# piezo-jfet-buffer-simple-4x.net
KiCad netlist of a schematic drawn in EAGLE
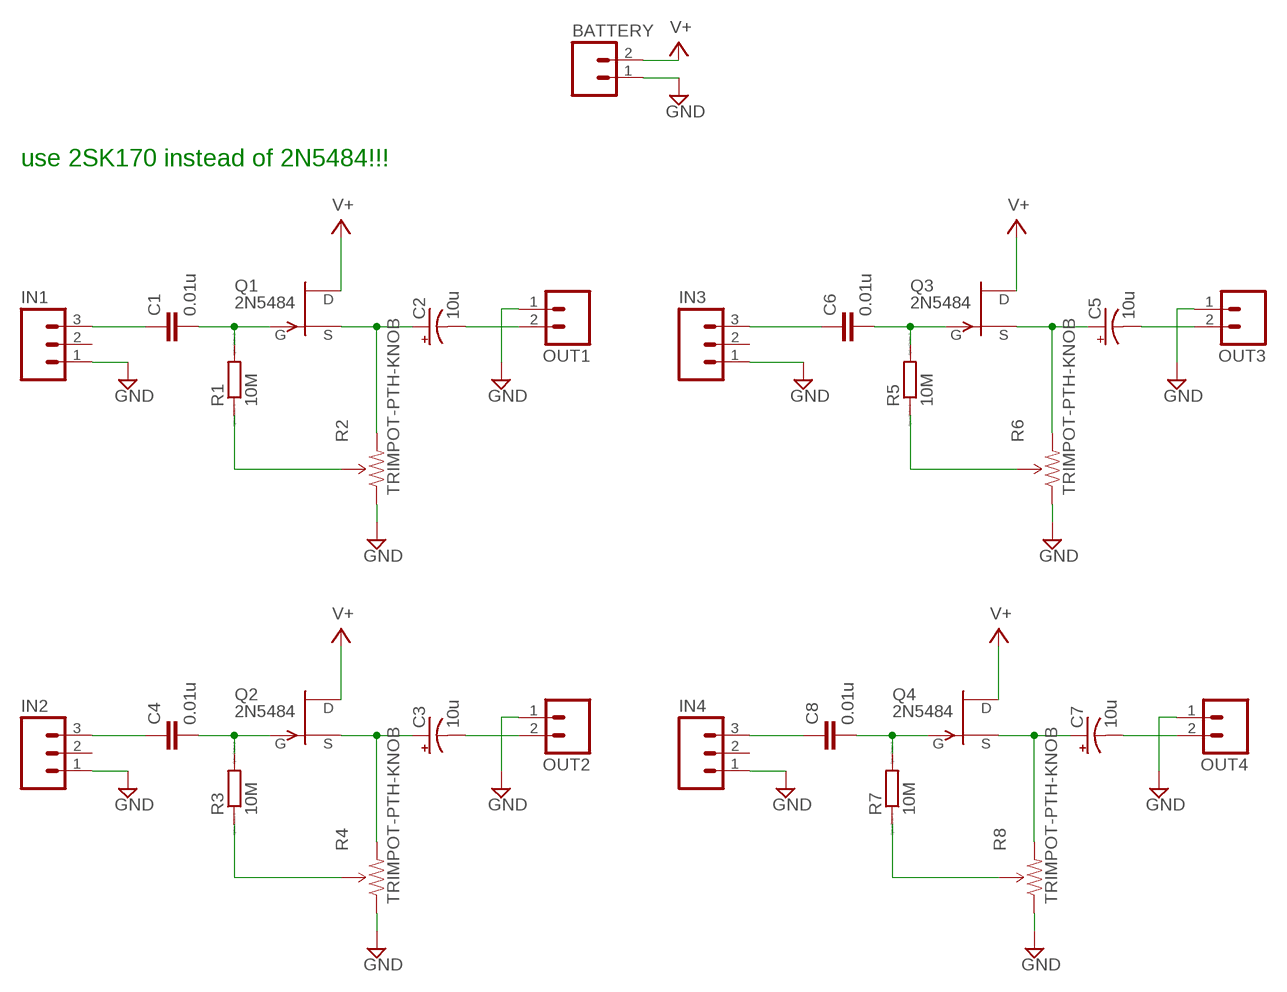
[diagram p0: schematic, sheet 1]

(export (version "E")
  (design (tool "Eeschema 10.0.6"))
  (components
    (comp (ref "BATTERY")
      (value "M02PTH")
      (footprint "eagle-import:1X02")
      (libsource (lib "eagle-import") (part "M02PTH"))
    )
    (comp (ref "C1")
      (value "0.01u")
      (footprint "eagle-import:C5B3")
      (libsource (lib "eagle-import") (part "C5/3"))
    )
    (comp (ref "C2")
      (value "10u")
      (footprint "eagle-import:CPOL-RADIAL-10UF-25V")
      (libsource (lib "eagle-import") (part "CAP_POLPTH2"))
    )
    (comp (ref "C3")
      (value "10u")
      (footprint "eagle-import:CPOL-RADIAL-10UF-25V")
      (libsource (lib "eagle-import") (part "CAP_POLPTH2"))
    )
    (comp (ref "C4")
      (value "0.01u")
      (footprint "eagle-import:C5B3")
      (libsource (lib "eagle-import") (part "C5/3"))
    )
    (comp (ref "C5")
      (value "10u")
      (footprint "eagle-import:CPOL-RADIAL-10UF-25V")
      (libsource (lib "eagle-import") (part "CAP_POLPTH2"))
    )
    (comp (ref "C6")
      (value "0.01u")
      (footprint "eagle-import:C5B3")
      (libsource (lib "eagle-import") (part "C5/3"))
    )
    (comp (ref "C7")
      (value "10u")
      (footprint "eagle-import:CPOL-RADIAL-10UF-25V")
      (libsource (lib "eagle-import") (part "CAP_POLPTH2"))
    )
    (comp (ref "C8")
      (value "0.01u")
      (footprint "eagle-import:C5B3")
      (libsource (lib "eagle-import") (part "C5/3"))
    )
    (comp (ref "IN1")
      (value "M03LOCK")
      (footprint "eagle-import:1X03_LOCK")
      (libsource (lib "eagle-import") (part "M03LOCK"))
    )
    (comp (ref "IN2")
      (value "M03LOCK")
      (footprint "eagle-import:1X03_LOCK")
      (libsource (lib "eagle-import") (part "M03LOCK"))
    )
    (comp (ref "IN3")
      (value "M03LOCK")
      (footprint "eagle-import:1X03_LOCK")
      (libsource (lib "eagle-import") (part "M03LOCK"))
    )
    (comp (ref "IN4")
      (value "M03LOCK")
      (footprint "eagle-import:1X03_LOCK")
      (libsource (lib "eagle-import") (part "M03LOCK"))
    )
    (comp (ref "OUT1")
      (value "M02LOCK")
      (footprint "eagle-import:1X02_LOCK")
      (libsource (lib "eagle-import") (part "M02LOCK"))
    )
    (comp (ref "OUT2")
      (value "M02LOCK")
      (footprint "eagle-import:1X02_LOCK")
      (libsource (lib "eagle-import") (part "M02LOCK"))
    )
    (comp (ref "OUT3")
      (value "M02LOCK")
      (footprint "eagle-import:1X02_LOCK")
      (libsource (lib "eagle-import") (part "M02LOCK"))
    )
    (comp (ref "OUT4")
      (value "M02LOCK")
      (footprint "eagle-import:1X02_LOCK")
      (libsource (lib "eagle-import") (part "M02LOCK"))
    )
    (comp (ref "Q1")
      (value "2N5484")
      (footprint "eagle-import:TO92-")
      (libsource (lib "eagle-import") (part "?5482N4"))
    )
    (comp (ref "Q2")
      (value "2N5484")
      (footprint "eagle-import:TO92-")
      (libsource (lib "eagle-import") (part "?5482N4"))
    )
    (comp (ref "Q3")
      (value "2N5484")
      (footprint "eagle-import:TO92-")
      (libsource (lib "eagle-import") (part "?5482N4"))
    )
    (comp (ref "Q4")
      (value "2N5484")
      (footprint "eagle-import:TO92-")
      (libsource (lib "eagle-import") (part "?5482N4"))
    )
    (comp (ref "R1")
      (value "10M")
      (footprint "eagle-import:0204_7")
      (libsource (lib "eagle-import") (part "R0204/7"))
    )
    (comp (ref "R2")
      (value "TRIMPOT-PTH-KNOB")
      (footprint "eagle-import:3386U")
      (libsource (lib "eagle-import") (part "TRIMPOT-PTH-KNOB"))
    )
    (comp (ref "R3")
      (value "10M")
      (footprint "eagle-import:0204_7")
      (libsource (lib "eagle-import") (part "R0204/7"))
    )
    (comp (ref "R4")
      (value "TRIMPOT-PTH-KNOB")
      (footprint "eagle-import:3386U")
      (libsource (lib "eagle-import") (part "TRIMPOT-PTH-KNOB"))
    )
    (comp (ref "R5")
      (value "10M")
      (footprint "eagle-import:0204_7")
      (libsource (lib "eagle-import") (part "R0204/7"))
    )
    (comp (ref "R6")
      (value "TRIMPOT-PTH-KNOB")
      (footprint "eagle-import:3386U")
      (libsource (lib "eagle-import") (part "TRIMPOT-PTH-KNOB"))
    )
    (comp (ref "R7")
      (value "10M")
      (footprint "eagle-import:0204_7")
      (libsource (lib "eagle-import") (part "R0204/7"))
    )
    (comp (ref "R8")
      (value "TRIMPOT-PTH-KNOB")
      (footprint "eagle-import:3386U")
      (libsource (lib "eagle-import") (part "TRIMPOT-PTH-KNOB"))
    )
  )
  (nets
    (net (code "1") (name "GND") (class "Default")
      (node (ref "BATTERY") (pin "1") (pinfunction "1_1") (pintype "passive"))
      (node (ref "IN1") (pin "1") (pinfunction "1_1") (pintype "passive"))
      (node (ref "IN2") (pin "1") (pinfunction "1_1") (pintype "passive"))
      (node (ref "IN3") (pin "1") (pinfunction "1_1") (pintype "passive"))
      (node (ref "IN4") (pin "1") (pinfunction "1_1") (pintype "passive"))
      (node (ref "OUT1") (pin "1") (pinfunction "1_1") (pintype "passive"))
      (node (ref "OUT2") (pin "1") (pinfunction "1_1") (pintype "passive"))
      (node (ref "OUT3") (pin "1") (pinfunction "1_1") (pintype "passive"))
      (node (ref "OUT4") (pin "1") (pinfunction "1_1") (pintype "passive"))
      (node (ref "R2") (pin "1") (pinfunction "CCW_1") (pintype "passive"))
      (node (ref "R4") (pin "1") (pinfunction "CCW_1") (pintype "passive"))
      (node (ref "R6") (pin "1") (pinfunction "CCW_1") (pintype "passive"))
      (node (ref "R8") (pin "1") (pinfunction "CCW_1") (pintype "passive"))
    )
    (net (code "2") (name "Net-(C1-Pad1)") (class "Default")
      (node (ref "C1") (pin "1") (pinfunction "1_1") (pintype "passive"))
      (node (ref "IN1") (pin "3") (pinfunction "3_3") (pintype "passive"))
    )
    (net (code "3") (name "Net-(C2-+)") (class "Default")
      (node (ref "C2") (pin "1") (pinfunction "+_1") (pintype "passive"))
      (node (ref "Q1") (pin "2") (pinfunction "S_2") (pintype "passive"))
      (node (ref "R2") (pin "3") (pinfunction "CW_3") (pintype "passive"))
    )
    (net (code "4") (name "Net-(C2--)") (class "Default")
      (node (ref "C2") (pin "2") (pinfunction "-_2") (pintype "passive"))
      (node (ref "OUT1") (pin "2") (pinfunction "2_2") (pintype "passive"))
    )
    (net (code "5") (name "Net-(C3-+)") (class "Default")
      (node (ref "C3") (pin "1") (pinfunction "+_1") (pintype "passive"))
      (node (ref "Q2") (pin "2") (pinfunction "S_2") (pintype "passive"))
      (node (ref "R4") (pin "3") (pinfunction "CW_3") (pintype "passive"))
    )
    (net (code "6") (name "Net-(C3--)") (class "Default")
      (node (ref "C3") (pin "2") (pinfunction "-_2") (pintype "passive"))
      (node (ref "OUT2") (pin "2") (pinfunction "2_2") (pintype "passive"))
    )
    (net (code "7") (name "Net-(C4-Pad1)") (class "Default")
      (node (ref "C4") (pin "1") (pinfunction "1_1") (pintype "passive"))
      (node (ref "IN2") (pin "3") (pinfunction "3_3") (pintype "passive"))
    )
    (net (code "8") (name "Net-(C5-+)") (class "Default")
      (node (ref "C5") (pin "1") (pinfunction "+_1") (pintype "passive"))
      (node (ref "Q3") (pin "2") (pinfunction "S_2") (pintype "passive"))
      (node (ref "R6") (pin "3") (pinfunction "CW_3") (pintype "passive"))
    )
    (net (code "9") (name "Net-(C5--)") (class "Default")
      (node (ref "C5") (pin "2") (pinfunction "-_2") (pintype "passive"))
      (node (ref "OUT3") (pin "2") (pinfunction "2_2") (pintype "passive"))
    )
    (net (code "10") (name "Net-(C6-Pad1)") (class "Default")
      (node (ref "C6") (pin "1") (pinfunction "1_1") (pintype "passive"))
      (node (ref "IN3") (pin "3") (pinfunction "3_3") (pintype "passive"))
    )
    (net (code "11") (name "Net-(C7-+)") (class "Default")
      (node (ref "C7") (pin "1") (pinfunction "+_1") (pintype "passive"))
      (node (ref "Q4") (pin "2") (pinfunction "S_2") (pintype "passive"))
      (node (ref "R8") (pin "3") (pinfunction "CW_3") (pintype "passive"))
    )
    (net (code "12") (name "Net-(C7--)") (class "Default")
      (node (ref "C7") (pin "2") (pinfunction "-_2") (pintype "passive"))
      (node (ref "OUT4") (pin "2") (pinfunction "2_2") (pintype "passive"))
    )
    (net (code "13") (name "Net-(C8-Pad1)") (class "Default")
      (node (ref "C8") (pin "1") (pinfunction "1_1") (pintype "passive"))
      (node (ref "IN4") (pin "3") (pinfunction "3_3") (pintype "passive"))
    )
    (net (code "14") (name "Net-(Q1-G)") (class "Default")
      (node (ref "C1") (pin "2") (pinfunction "2_2") (pintype "passive"))
      (node (ref "Q1") (pin "1") (pinfunction "G_1") (pintype "passive"))
      (node (ref "R1") (pin "2") (pinfunction "2_2") (pintype "passive"))
    )
    (net (code "15") (name "Net-(Q2-G)") (class "Default")
      (node (ref "C4") (pin "2") (pinfunction "2_2") (pintype "passive"))
      (node (ref "Q2") (pin "1") (pinfunction "G_1") (pintype "passive"))
      (node (ref "R3") (pin "2") (pinfunction "2_2") (pintype "passive"))
    )
    (net (code "16") (name "Net-(Q3-G)") (class "Default")
      (node (ref "C6") (pin "2") (pinfunction "2_2") (pintype "passive"))
      (node (ref "Q3") (pin "1") (pinfunction "G_1") (pintype "passive"))
      (node (ref "R5") (pin "2") (pinfunction "2_2") (pintype "passive"))
    )
    (net (code "17") (name "Net-(Q4-G)") (class "Default")
      (node (ref "C8") (pin "2") (pinfunction "2_2") (pintype "passive"))
      (node (ref "Q4") (pin "1") (pinfunction "G_1") (pintype "passive"))
      (node (ref "R7") (pin "2") (pinfunction "2_2") (pintype "passive"))
    )
    (net (code "18") (name "Net-(R2-WIPER)") (class "Default")
      (node (ref "R1") (pin "1") (pinfunction "1_1") (pintype "passive"))
      (node (ref "R2") (pin "2") (pinfunction "WIPER_2") (pintype "passive"))
    )
    (net (code "19") (name "Net-(R4-WIPER)") (class "Default")
      (node (ref "R3") (pin "1") (pinfunction "1_1") (pintype "passive"))
      (node (ref "R4") (pin "2") (pinfunction "WIPER_2") (pintype "passive"))
    )
    (net (code "20") (name "Net-(R6-WIPER)") (class "Default")
      (node (ref "R5") (pin "1") (pinfunction "1_1") (pintype "passive"))
      (node (ref "R6") (pin "2") (pinfunction "WIPER_2") (pintype "passive"))
    )
    (net (code "21") (name "Net-(R8-WIPER)") (class "Default")
      (node (ref "R7") (pin "1") (pinfunction "1_1") (pintype "passive"))
      (node (ref "R8") (pin "2") (pinfunction "WIPER_2") (pintype "passive"))
    )
    (net (code "22") (name "V+") (class "Default")
      (node (ref "BATTERY") (pin "2") (pinfunction "2_2") (pintype "passive"))
      (node (ref "Q1") (pin "3") (pinfunction "D_3") (pintype "passive"))
      (node (ref "Q2") (pin "3") (pinfunction "D_3") (pintype "passive"))
      (node (ref "Q3") (pin "3") (pinfunction "D_3") (pintype "passive"))
      (node (ref "Q4") (pin "3") (pinfunction "D_3") (pintype "passive"))
    )
    (net (code "23") (name "unconnected-(IN1-Pad2)") (class "Default")
      (node (ref "IN1") (pin "2") (pinfunction "2_2") (pintype "passive"))
    )
    (net (code "24") (name "unconnected-(IN2-Pad2)") (class "Default")
      (node (ref "IN2") (pin "2") (pinfunction "2_2") (pintype "passive"))
    )
    (net (code "25") (name "unconnected-(IN3-Pad2)") (class "Default")
      (node (ref "IN3") (pin "2") (pinfunction "2_2") (pintype "passive"))
    )
    (net (code "26") (name "unconnected-(IN4-Pad2)") (class "Default")
      (node (ref "IN4") (pin "2") (pinfunction "2_2") (pintype "passive"))
    )
  )
)
